# stm32G031J6M6-Breakout.net
KiCad netlist of a schematic drawn in EAGLE
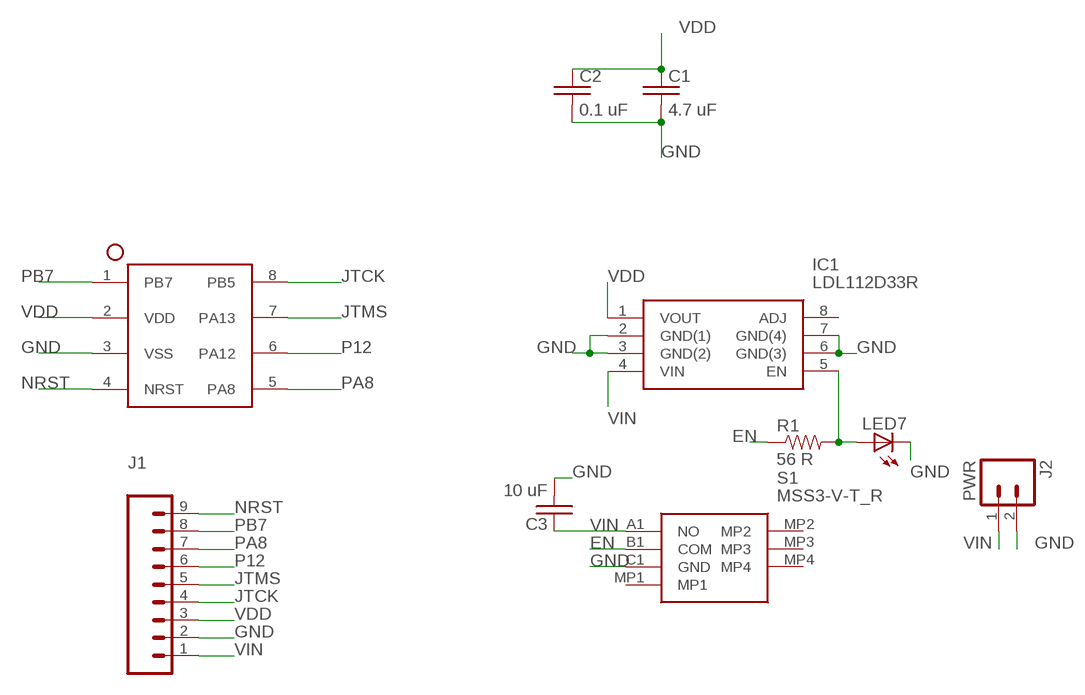
[diagram p0: schematic, sheet 1]

(export (version "E")
  (design (tool "Eeschema 10.0.6"))
  (components
    (comp (ref "C1")
      (value "4.7 uF")
      (footprint "eagle-import:C0805K")
      (libsource (lib "eagle-import") (part "C-USC0805K"))
    )
    (comp (ref "C2")
      (value "0.1 uF")
      (footprint "eagle-import:C0805K")
      (libsource (lib "eagle-import") (part "C-USC0805K"))
    )
    (comp (ref "C3")
      (value "10 uF")
      (footprint "eagle-import:C0805K")
      (libsource (lib "eagle-import") (part "C-USC0805K"))
    )
    (comp (ref "IC1")
      (value "LDL112D33R")
      (footprint "eagle-import:SOIC127P600X175-8N")
      (libsource (lib "eagle-import") (part "LDL112D33R"))
    )
    (comp (ref "J1")
      (value "M09LONGPADS")
      (footprint "eagle-import:1X09_LONGPADS")
      (libsource (lib "eagle-import") (part "M09LONGPADS"))
    )
    (comp (ref "J2")
      (value "PWR")
      (footprint "eagle-import:SCREWTERMINAL-5MM-2")
      (libsource (lib "eagle-import") (part "M025MM"))
    )
    (comp (ref "LED7")
      (value "LED1206")
      (footprint "eagle-import:LED-1206")
      (libsource (lib "eagle-import") (part "LED1206"))
    )
    (comp (ref "R1")
      (value "56 R")
      (footprint "eagle-import:1206")
      (libsource (lib "eagle-import") (part "RESISTOR1206"))
    )
    (comp (ref "S1")
      (value "MSS3-V-T_R")
      (footprint "eagle-import:MSS3VTR")
      (fields
        (field (name "MANUFACTURER_PART_NUMBER") "MSS3-V-T/R")
        (field (name "MOUSER_PART_NUMBER") "113-MSS3-V-T/R")
      )
      (libsource (lib "eagle-import") (part "MSS3-V-T_R"))
    )
    (comp (ref "U$1")
      (value "STM32G031S08N")
      (footprint "eagle-import:SOIC127P600X175-8N")
      (libsource (lib "eagle-import") (part "STM32G031S08N"))
    )
  )
  (nets
    (net (code "1") (name "/EN") (class "Default")
      (node (ref "R1") (pin "1") (pinfunction "1_1") (pintype "passive"))
      (node (ref "S1") (pin "B1") (pinfunction "COM_B1") (pintype "bidirectional"))
    )
    (net (code "2") (name "/GND") (class "Default")
      (node (ref "C1") (pin "2") (pinfunction "2_2") (pintype "passive"))
      (node (ref "C2") (pin "2") (pinfunction "2_2") (pintype "passive"))
      (node (ref "C3") (pin "2") (pinfunction "2_2") (pintype "passive"))
      (node (ref "IC1") (pin "2") (pinfunction "GND(1)_2") (pintype "bidirectional"))
      (node (ref "IC1") (pin "3") (pinfunction "GND(2)_3") (pintype "bidirectional"))
      (node (ref "IC1") (pin "6") (pinfunction "GND(3)_6") (pintype "bidirectional"))
      (node (ref "IC1") (pin "7") (pinfunction "GND(4)_7") (pintype "bidirectional"))
      (node (ref "J1") (pin "2") (pinfunction "2_2") (pintype "passive"))
      (node (ref "J2") (pin "2") (pinfunction "2_2") (pintype "passive"))
      (node (ref "LED7") (pin "C") (pinfunction "C_C") (pintype "output"))
      (node (ref "S1") (pin "C1") (pinfunction "GND_C1") (pintype "bidirectional"))
      (node (ref "U$1") (pin "3") (pinfunction "VSS_3") (pintype "power_in"))
    )
    (net (code "3") (name "/JTCK") (class "Default")
      (node (ref "J1") (pin "4") (pinfunction "4_4") (pintype "passive"))
      (node (ref "U$1") (pin "8") (pinfunction "PB5_8") (pintype "bidirectional"))
    )
    (net (code "4") (name "/JTMS") (class "Default")
      (node (ref "J1") (pin "5") (pinfunction "5_5") (pintype "passive"))
      (node (ref "U$1") (pin "7") (pinfunction "PA13_7") (pintype "bidirectional"))
    )
    (net (code "5") (name "/NRST") (class "Default")
      (node (ref "J1") (pin "9") (pinfunction "9_9") (pintype "passive"))
      (node (ref "U$1") (pin "4") (pinfunction "NRST_4") (pintype "bidirectional"))
    )
    (net (code "6") (name "/P12") (class "Default")
      (node (ref "J1") (pin "6") (pinfunction "6_6") (pintype "passive"))
      (node (ref "U$1") (pin "6") (pinfunction "PA12_6") (pintype "bidirectional"))
    )
    (net (code "7") (name "/PA8") (class "Default")
      (node (ref "J1") (pin "7") (pinfunction "7_7") (pintype "passive"))
      (node (ref "U$1") (pin "5") (pinfunction "PA8_5") (pintype "bidirectional"))
    )
    (net (code "8") (name "/PB7") (class "Default")
      (node (ref "J1") (pin "8") (pinfunction "8_8") (pintype "passive"))
      (node (ref "U$1") (pin "1") (pinfunction "PB7_1") (pintype "bidirectional"))
    )
    (net (code "9") (name "/VDD") (class "Default")
      (node (ref "C1") (pin "1") (pinfunction "1_1") (pintype "passive"))
      (node (ref "C2") (pin "1") (pinfunction "1_1") (pintype "passive"))
      (node (ref "IC1") (pin "1") (pinfunction "VOUT_1") (pintype "bidirectional"))
      (node (ref "J1") (pin "3") (pinfunction "3_3") (pintype "passive"))
      (node (ref "U$1") (pin "2") (pinfunction "VDD_2") (pintype "power_in"))
    )
    (net (code "10") (name "/VIN") (class "Default")
      (node (ref "C3") (pin "1") (pinfunction "1_1") (pintype "passive"))
      (node (ref "IC1") (pin "4") (pinfunction "VIN_4") (pintype "bidirectional"))
      (node (ref "J1") (pin "1") (pinfunction "1_1") (pintype "passive"))
      (node (ref "J2") (pin "1") (pinfunction "1_1") (pintype "passive"))
      (node (ref "S1") (pin "A1") (pinfunction "NO_A1") (pintype "bidirectional"))
    )
    (net (code "11") (name "Net-(IC1-EN)") (class "Default")
      (node (ref "IC1") (pin "5") (pinfunction "EN_5") (pintype "bidirectional"))
      (node (ref "LED7") (pin "A") (pinfunction "A_A") (pintype "input"))
      (node (ref "R1") (pin "2") (pinfunction "2_2") (pintype "passive"))
    )
    (net (code "12") (name "unconnected-(IC1-ADJ-Pad8)") (class "Default")
      (node (ref "IC1") (pin "8") (pinfunction "ADJ_8") (pintype "bidirectional"))
    )
    (net (code "13") (name "unconnected-(S1-PadMP1)") (class "Default")
      (node (ref "S1") (pin "MP1") (pinfunction "MP1_MP1") (pintype "bidirectional"))
    )
    (net (code "14") (name "unconnected-(S1-PadMP2)") (class "Default")
      (node (ref "S1") (pin "MP2") (pinfunction "MP2_MP2") (pintype "bidirectional"))
    )
    (net (code "15") (name "unconnected-(S1-PadMP3)") (class "Default")
      (node (ref "S1") (pin "MP3") (pinfunction "MP3_MP3") (pintype "bidirectional"))
    )
    (net (code "16") (name "unconnected-(S1-PadMP4)") (class "Default")
      (node (ref "S1") (pin "MP4") (pinfunction "MP4_MP4") (pintype "bidirectional"))
    )
  )
)
